# SCH_PCB-Hacker-Card_2024-03-30.net
KiCad netlist of a schematic drawn in EasyEDA
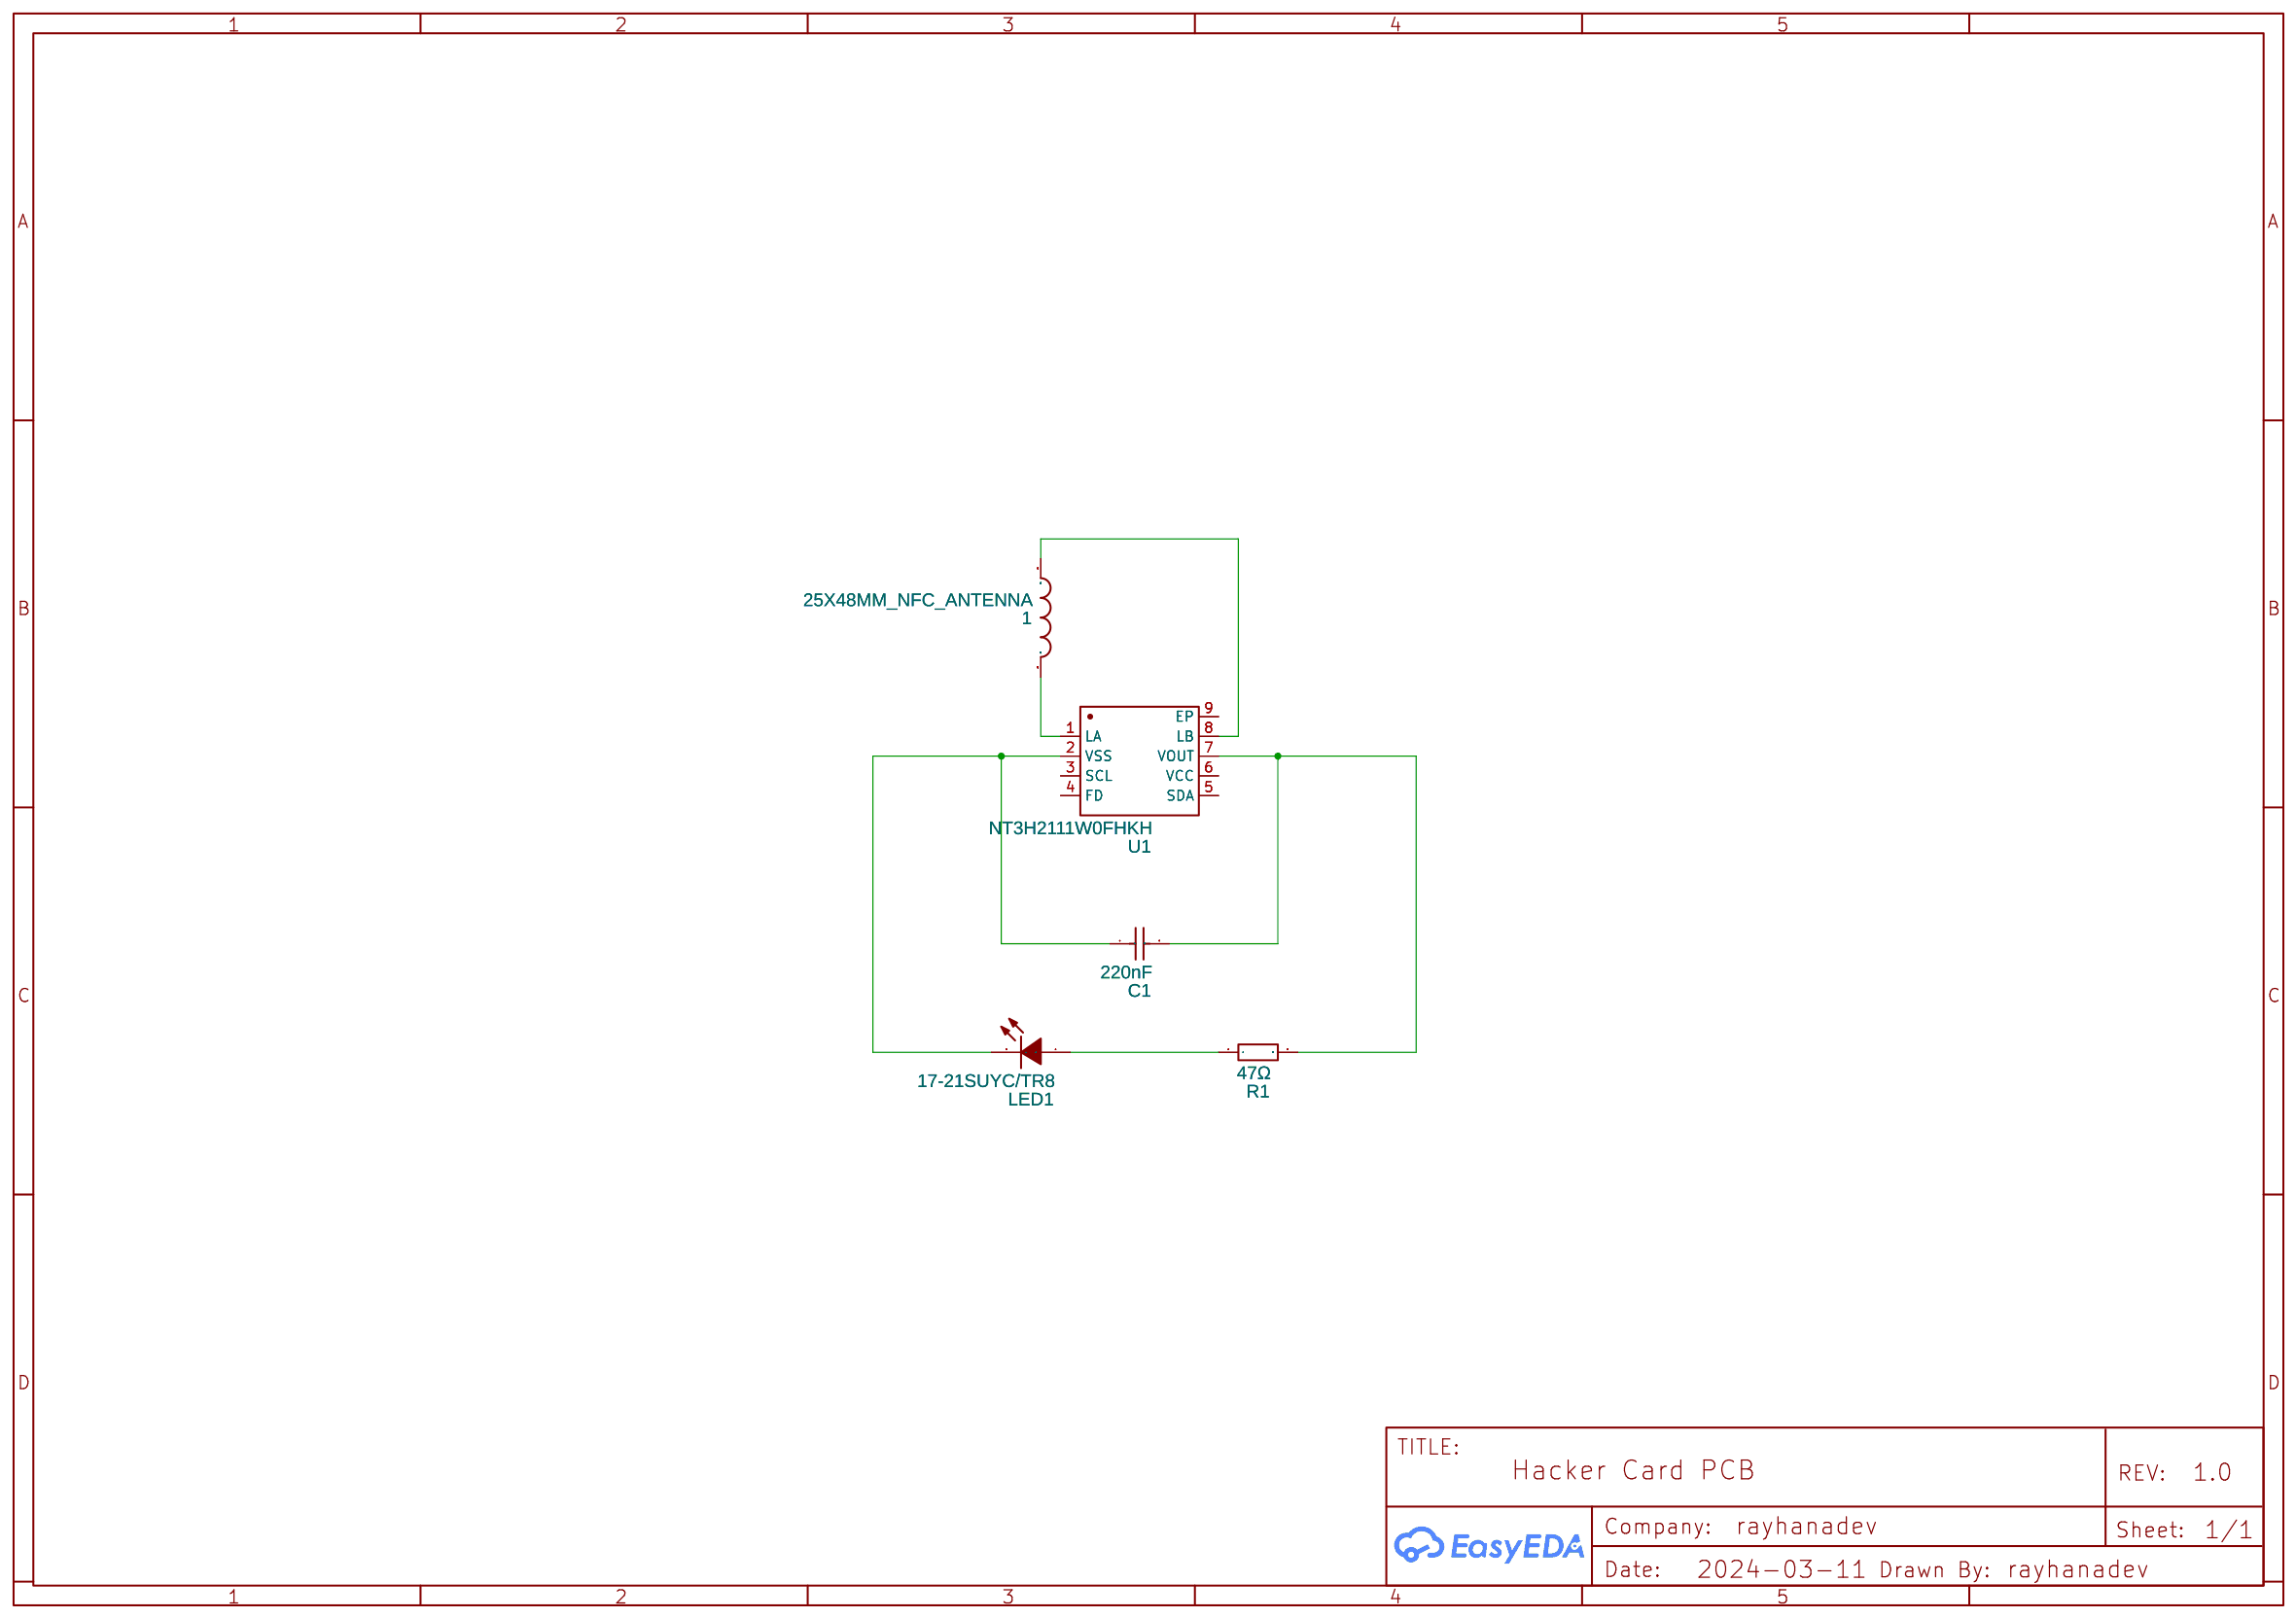
[diagram p0: schematic sheet]

(export (version "E")
  (design (tool "Eeschema 10.0.6"))
  (components
    (comp (ref "1") (value "25X48MM_NFC_ANTENNA") (libsource (lib "") (part "25X48MM_NFC_ANTENNA")))
    (comp (ref "C1")
      (value "220nF")
      (fields
        (field (name "Manufacturer Part") "CL10B224KA8NNNC")
        (field (name "Manufacturer") "SAMSUNG(三星)")
      )
      (libsource (lib "") (part "CL10B224KA8NNNC"))
    )
    (comp (ref "LED1")
      (value "17-21SUYC/TR8")
      (fields (field (name "Manufacturer Part") "KT-0805黄灯") (field (name "Manufacturer") "KENTO"))
      (libsource (lib "") (part "17-21SUYC/TR8"))
    )
    (comp (ref "R1")
      (value "47Ω")
      (fields
        (field (name "Manufacturer Part") "0603WAF470JT5E")
        (field (name "Manufacturer") "UNI-ROYAL(厚声)")
      )
      (libsource (lib "") (part "0603WAF470JT5E"))
    )
    (comp (ref "U1")
      (value "NT3H2111W0FHKH")
      (fields (field (name "Manufacturer") "NXP(恩智浦)"))
      (libsource (lib "") (part "NT3H2111W0FHKH"))
    )
  )
  (nets
    (net (code "1") (name "Net-(LED1-+)") (class "Default")
      (node (ref "LED1") (pin "1") (pinfunction "+_1") (pintype "unspecified"))
      (node (ref "R1") (pin "1") (pinfunction "1_1") (pintype "input"))
    )
    (net (code "2") (name "Net-(LED1--)") (class "Default")
      (node (ref "C1") (pin "1") (pinfunction "1_1") (pintype "input"))
      (node (ref "LED1") (pin "2") (pinfunction "-_2") (pintype "unspecified"))
      (node (ref "U1") (pin "2") (pinfunction "VSS_2") (pintype "unspecified"))
    )
    (net (code "3") (name "Net-(U1-LA)") (class "Default")
      (node (ref "1") (pin "P$2") (pinfunction "P$2_P$2") (pintype "bidirectional"))
      (node (ref "U1") (pin "1") (pinfunction "LA_1") (pintype "unspecified"))
    )
    (net (code "4") (name "Net-(U1-LB)") (class "Default")
      (node (ref "1") (pin "P$1") (pinfunction "P$1_P$1") (pintype "bidirectional"))
      (node (ref "U1") (pin "8") (pinfunction "LB_8") (pintype "unspecified"))
    )
    (net (code "5") (name "Net-(U1-VOUT)") (class "Default")
      (node (ref "C1") (pin "2") (pinfunction "2_2") (pintype "input"))
      (node (ref "R1") (pin "2") (pinfunction "2_2") (pintype "input"))
      (node (ref "U1") (pin "7") (pinfunction "VOUT_7") (pintype "unspecified"))
    )
    (net (code "6") (name "unconnected-(U1-EP-Pad9)") (class "Default")
      (node (ref "U1") (pin "9") (pinfunction "EP_9") (pintype "unspecified"))
    )
    (net (code "7") (name "unconnected-(U1-FD-Pad4)") (class "Default")
      (node (ref "U1") (pin "4") (pinfunction "FD_4") (pintype "unspecified"))
    )
    (net (code "8") (name "unconnected-(U1-SCL-Pad3)") (class "Default")
      (node (ref "U1") (pin "3") (pinfunction "SCL_3") (pintype "unspecified"))
    )
    (net (code "9") (name "unconnected-(U1-SDA-Pad5)") (class "Default")
      (node (ref "U1") (pin "5") (pinfunction "SDA_5") (pintype "unspecified"))
    )
    (net (code "10") (name "unconnected-(U1-VCC-Pad6)") (class "Default")
      (node (ref "U1") (pin "6") (pinfunction "VCC_6") (pintype "unspecified"))
    )
  )
)
